# Rev_B.net
KiCad netlist of a schematic drawn in EAGLE
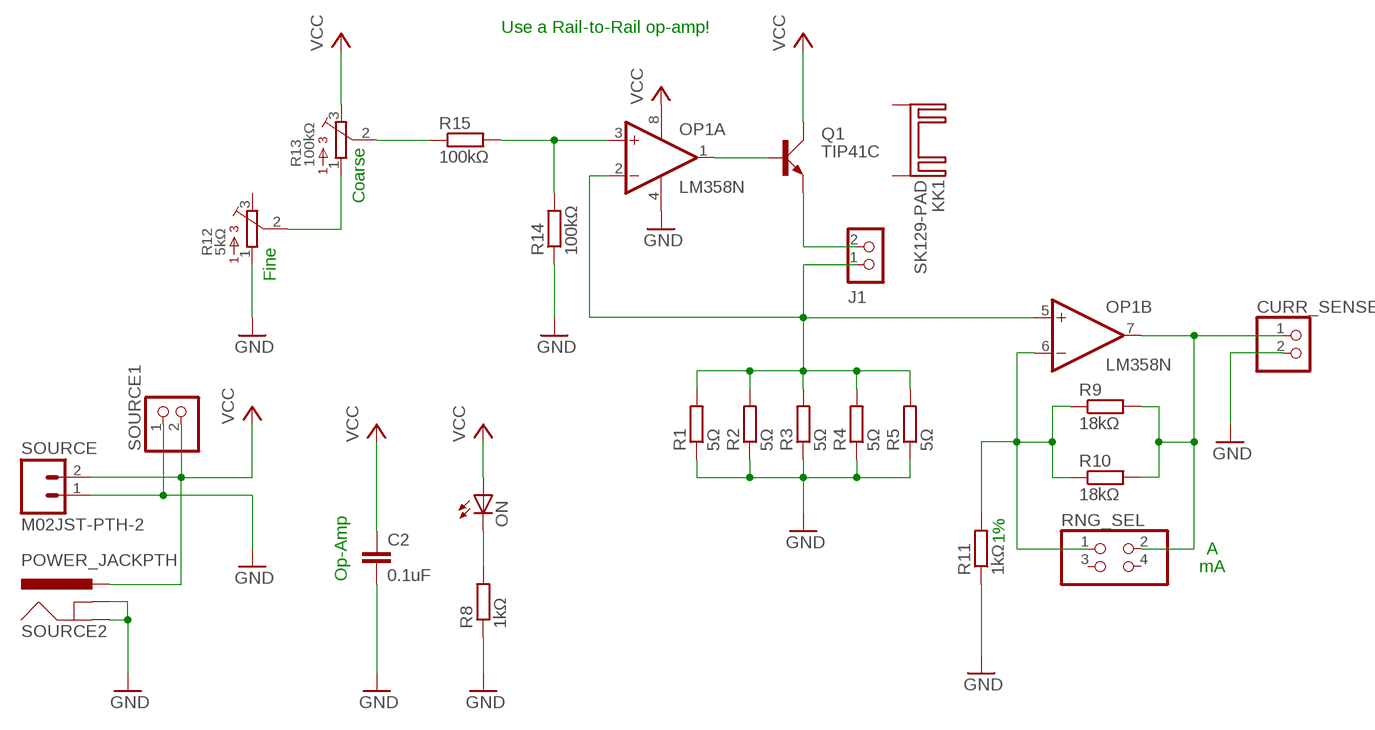
[diagram p0: schematic, sheet 1]

(export (version "E")
  (design (tool "Eeschema 10.0.6"))
  (components
    (comp (ref "C2")
      (value "0.1uF")
      (footprint "eagle-import:C050-025X075")
      (libsource (lib "eagle-import") (part "C-EU050-025X075"))
    )
    (comp (ref "CURR_SENSE")
      (value "PINHD-1X2")
      (footprint "eagle-import:1X02")
      (libsource (lib "eagle-import") (part "PINHD-1X2"))
    )
    (comp (ref "J1")
      (value "CON_TERMINAL_BLOCK_02-5MM")
      (footprint "eagle-import:TERMINAL_BLOCK_2P_5")
      (libsource (lib "eagle-import") (part "CON_TERMINAL_BLOCK_02-5MM"))
    )
    (comp (ref "KK1")
      (value "SK129-PAD")
      (footprint "eagle-import:SK129")
      (libsource (lib "eagle-import") (part "SK129-PAD"))
    )
    (comp (ref "ON")
      (value "LEDSQR2X5")
      (footprint "eagle-import:LED2X5")
      (libsource (lib "eagle-import") (part "LEDSQR2X5"))
    )
    (comp (ref "OP1")
      (value "LM358N")
      (footprint "eagle-import:DIL08")
      (libsource (lib "eagle-import") (part "LM358N"))
    )
    (comp (ref "Q1")
      (value "TIP41C")
      (footprint "eagle-import:TO220AV")
      (libsource (lib "eagle-import") (part "TIP41C"))
    )
    (comp (ref "R1")
      (value "5Ω")
      (footprint "eagle-import:P0613_15")
      (libsource (lib "eagle-import") (part "R-EU_0613/15"))
    )
    (comp (ref "R2")
      (value "5Ω")
      (footprint "eagle-import:P0613_15")
      (libsource (lib "eagle-import") (part "R-EU_0613/15"))
    )
    (comp (ref "R3")
      (value "5Ω")
      (footprint "eagle-import:P0613_15")
      (libsource (lib "eagle-import") (part "R-EU_0613/15"))
    )
    (comp (ref "R4")
      (value "5Ω")
      (footprint "eagle-import:P0613_15")
      (libsource (lib "eagle-import") (part "R-EU_0613/15"))
    )
    (comp (ref "R5")
      (value "5Ω")
      (footprint "eagle-import:P0613_15")
      (libsource (lib "eagle-import") (part "R-EU_0613/15"))
    )
    (comp (ref "R8")
      (value "1kΩ")
      (footprint "eagle-import:0207_10")
      (libsource (lib "eagle-import") (part "R-EU_0207/10"))
    )
    (comp (ref "R9")
      (value "18kΩ")
      (footprint "eagle-import:0207_10")
      (libsource (lib "eagle-import") (part "resistor_R-EU_0207/10"))
    )
    (comp (ref "R10")
      (value "18kΩ")
      (footprint "eagle-import:0207_10")
      (libsource (lib "eagle-import") (part "resistor_R-EU_0207/10"))
    )
    (comp (ref "R11")
      (value "1kΩ")
      (footprint "eagle-import:0207_10")
      (libsource (lib "eagle-import") (part "resistor_R-EU_0207/10"))
    )
    (comp (ref "R12")
      (value "5kΩ")
      (footprint "eagle-import:3362U")
      (libsource (lib "eagle-import") (part "3362U"))
    )
    (comp (ref "R13")
      (value "100kΩ")
      (footprint "eagle-import:3362U")
      (libsource (lib "eagle-import") (part "3362U"))
    )
    (comp (ref "R14")
      (value "100kΩ")
      (footprint "eagle-import:0207_10")
      (libsource (lib "eagle-import") (part "resistor_R-EU_0207/10"))
    )
    (comp (ref "R15")
      (value "100kΩ")
      (footprint "eagle-import:0207_10")
      (libsource (lib "eagle-import") (part "resistor_R-EU_0207/10"))
    )
    (comp (ref "RNG_SEL")
      (value "PINHD-2X2")
      (footprint "eagle-import:2X02")
      (libsource (lib "eagle-import") (part "PINHD-2X2"))
    )
    (comp (ref "SOURCE")
      (value "M02JST-PTH-2")
      (footprint "eagle-import:JST-2-PTH")
      (libsource (lib "eagle-import") (part "M02JST-PTH-2"))
    )
    (comp (ref "SOURCE1")
      (value "PINHD-1X2")
      (footprint "eagle-import:1X02")
      (libsource (lib "eagle-import") (part "PINHD-1X2"))
    )
    (comp (ref "SOURCE2")
      (value "POWER_JACKPTH")
      (footprint "eagle-import:POWER_JACK_PTH")
      (libsource (lib "eagle-import") (part "POWER_JACKPTH"))
    )
  )
  (nets
    (net (code "1") (name "GND") (class "Default")
      (node (ref "C2") (pin "2") (pinfunction "2_2") (pintype "passive"))
      (node (ref "CURR_SENSE") (pin "2") (pinfunction "2_2") (pintype "passive"))
      (node (ref "OP1") (pin "4") (pinfunction "V-_4") (pintype "power_in"))
      (node (ref "R1") (pin "1") (pinfunction "1_1") (pintype "passive"))
      (node (ref "R11") (pin "1") (pinfunction "1_1") (pintype "passive"))
      (node (ref "R12") (pin "1") (pinfunction "1_1") (pintype "passive"))
      (node (ref "R14") (pin "1") (pinfunction "1_1") (pintype "passive"))
      (node (ref "R2") (pin "1") (pinfunction "1_1") (pintype "passive"))
      (node (ref "R3") (pin "1") (pinfunction "1_1") (pintype "passive"))
      (node (ref "R4") (pin "1") (pinfunction "1_1") (pintype "passive"))
      (node (ref "R5") (pin "1") (pinfunction "1_1") (pintype "passive"))
      (node (ref "R8") (pin "1") (pinfunction "1_1") (pintype "passive"))
      (node (ref "SOURCE") (pin "1") (pinfunction "1_1") (pintype "passive"))
      (node (ref "SOURCE1") (pin "1") (pinfunction "1_1") (pintype "passive"))
      (node (ref "SOURCE2") (pin "GND") (pinfunction "GND_GND") (pintype "bidirectional"))
      (node (ref "SOURCE2") (pin "GNDBREAK") (pinfunction "GNDBREAK_GNDBREAK") (pintype "bidirectional"))
    )
    (net (code "2") (name "Net-(J1-Pad2)") (class "Default")
      (node (ref "J1") (pin "2") (pinfunction "2_2") (pintype "passive"))
      (node (ref "Q1") (pin "E") (pinfunction "E_E") (pintype "passive"))
    )
    (net (code "3") (name "Net-(ON-C)") (class "Default")
      (node (ref "ON") (pin "K") (pinfunction "C_K") (pintype "passive"))
      (node (ref "R8") (pin "2") (pinfunction "2_2") (pintype "passive"))
    )
    (net (code "4") (name "Net-(OP1A-+IN)") (class "Default")
      (node (ref "OP1") (pin "3") (pinfunction "+IN_3") (pintype "input"))
      (node (ref "R14") (pin "2") (pinfunction "2_2") (pintype "passive"))
      (node (ref "R15") (pin "2") (pinfunction "2_2") (pintype "passive"))
    )
    (net (code "5") (name "Net-(OP1A--IN)") (class "Default")
      (node (ref "J1") (pin "1") (pinfunction "1_1") (pintype "passive"))
      (node (ref "OP1") (pin "2") (pinfunction "-IN_2") (pintype "input"))
      (node (ref "OP1") (pin "5") (pinfunction "+IN_5") (pintype "input"))
      (node (ref "R1") (pin "2") (pinfunction "2_2") (pintype "passive"))
      (node (ref "R2") (pin "2") (pinfunction "2_2") (pintype "passive"))
      (node (ref "R3") (pin "2") (pinfunction "2_2") (pintype "passive"))
      (node (ref "R4") (pin "2") (pinfunction "2_2") (pintype "passive"))
      (node (ref "R5") (pin "2") (pinfunction "2_2") (pintype "passive"))
    )
    (net (code "6") (name "Net-(OP1A-OUT)") (class "Default")
      (node (ref "OP1") (pin "1") (pinfunction "OUT_1") (pintype "output"))
      (node (ref "Q1") (pin "B") (pinfunction "B_B") (pintype "passive"))
    )
    (net (code "7") (name "Net-(OP1B--IN)") (class "Default")
      (node (ref "OP1") (pin "6") (pinfunction "-IN_6") (pintype "input"))
      (node (ref "R10") (pin "1") (pinfunction "1_1") (pintype "passive"))
      (node (ref "R11") (pin "2") (pinfunction "2_2") (pintype "passive"))
      (node (ref "R9") (pin "1") (pinfunction "1_1") (pintype "passive"))
      (node (ref "RNG_SEL") (pin "1") (pinfunction "1_1") (pintype "passive"))
    )
    (net (code "8") (name "Net-(OP1B-OUT)") (class "Default")
      (node (ref "CURR_SENSE") (pin "1") (pinfunction "1_1") (pintype "passive"))
      (node (ref "OP1") (pin "7") (pinfunction "OUT_7") (pintype "output"))
      (node (ref "R10") (pin "2") (pinfunction "2_2") (pintype "passive"))
      (node (ref "R9") (pin "2") (pinfunction "2_2") (pintype "passive"))
      (node (ref "RNG_SEL") (pin "2") (pinfunction "2_2") (pintype "passive"))
    )
    (net (code "9") (name "Net-(R12-Pad2)") (class "Default")
      (node (ref "R12") (pin "2") (pinfunction "2_2") (pintype "passive"))
      (node (ref "R13") (pin "1") (pinfunction "1_1") (pintype "passive"))
    )
    (net (code "10") (name "Net-(R13-Pad2)") (class "Default")
      (node (ref "R13") (pin "2") (pinfunction "2_2") (pintype "passive"))
      (node (ref "R15") (pin "1") (pinfunction "1_1") (pintype "passive"))
    )
    (net (code "11") (name "VCC") (class "Default")
      (node (ref "C2") (pin "1") (pinfunction "1_1") (pintype "passive"))
      (node (ref "ON") (pin "A") (pinfunction "A_A") (pintype "passive"))
      (node (ref "OP1") (pin "8") (pinfunction "V+_8") (pintype "power_in"))
      (node (ref "Q1") (pin "C") (pinfunction "C_C") (pintype "passive"))
      (node (ref "R13") (pin "3") (pinfunction "3_3") (pintype "passive"))
      (node (ref "SOURCE") (pin "2") (pinfunction "2_2") (pintype "passive"))
      (node (ref "SOURCE1") (pin "2") (pinfunction "2_2") (pintype "passive"))
      (node (ref "SOURCE2") (pin "PWR") (pinfunction "PWR_PWR") (pintype "bidirectional"))
    )
    (net (code "12") (name "unconnected-(KK1-K-PadA2,5)") (class "Default")
      (node (ref "KK1") (pin "A2,5") (pinfunction "K_A2,5") (pintype "passive"))
    )
    (net (code "13") (name "unconnected-(KK1-K-PadB2,5)") (class "Default")
      (node (ref "KK1") (pin "B2,5") (pinfunction "K_B2,5") (pintype "passive"))
    )
    (net (code "14") (name "unconnected-(R12-Pad3)") (class "Default")
      (node (ref "R12") (pin "3") (pinfunction "3_3") (pintype "passive"))
    )
    (net (code "15") (name "unconnected-(RNG_SEL-Pad3)") (class "Default")
      (node (ref "RNG_SEL") (pin "3") (pinfunction "3_3") (pintype "passive"))
    )
    (net (code "16") (name "unconnected-(RNG_SEL-Pad4)") (class "Default")
      (node (ref "RNG_SEL") (pin "4") (pinfunction "4_4") (pintype "passive"))
    )
  )
)
